# CV_Pot.net
KiCad netlist of a schematic drawn in EAGLE
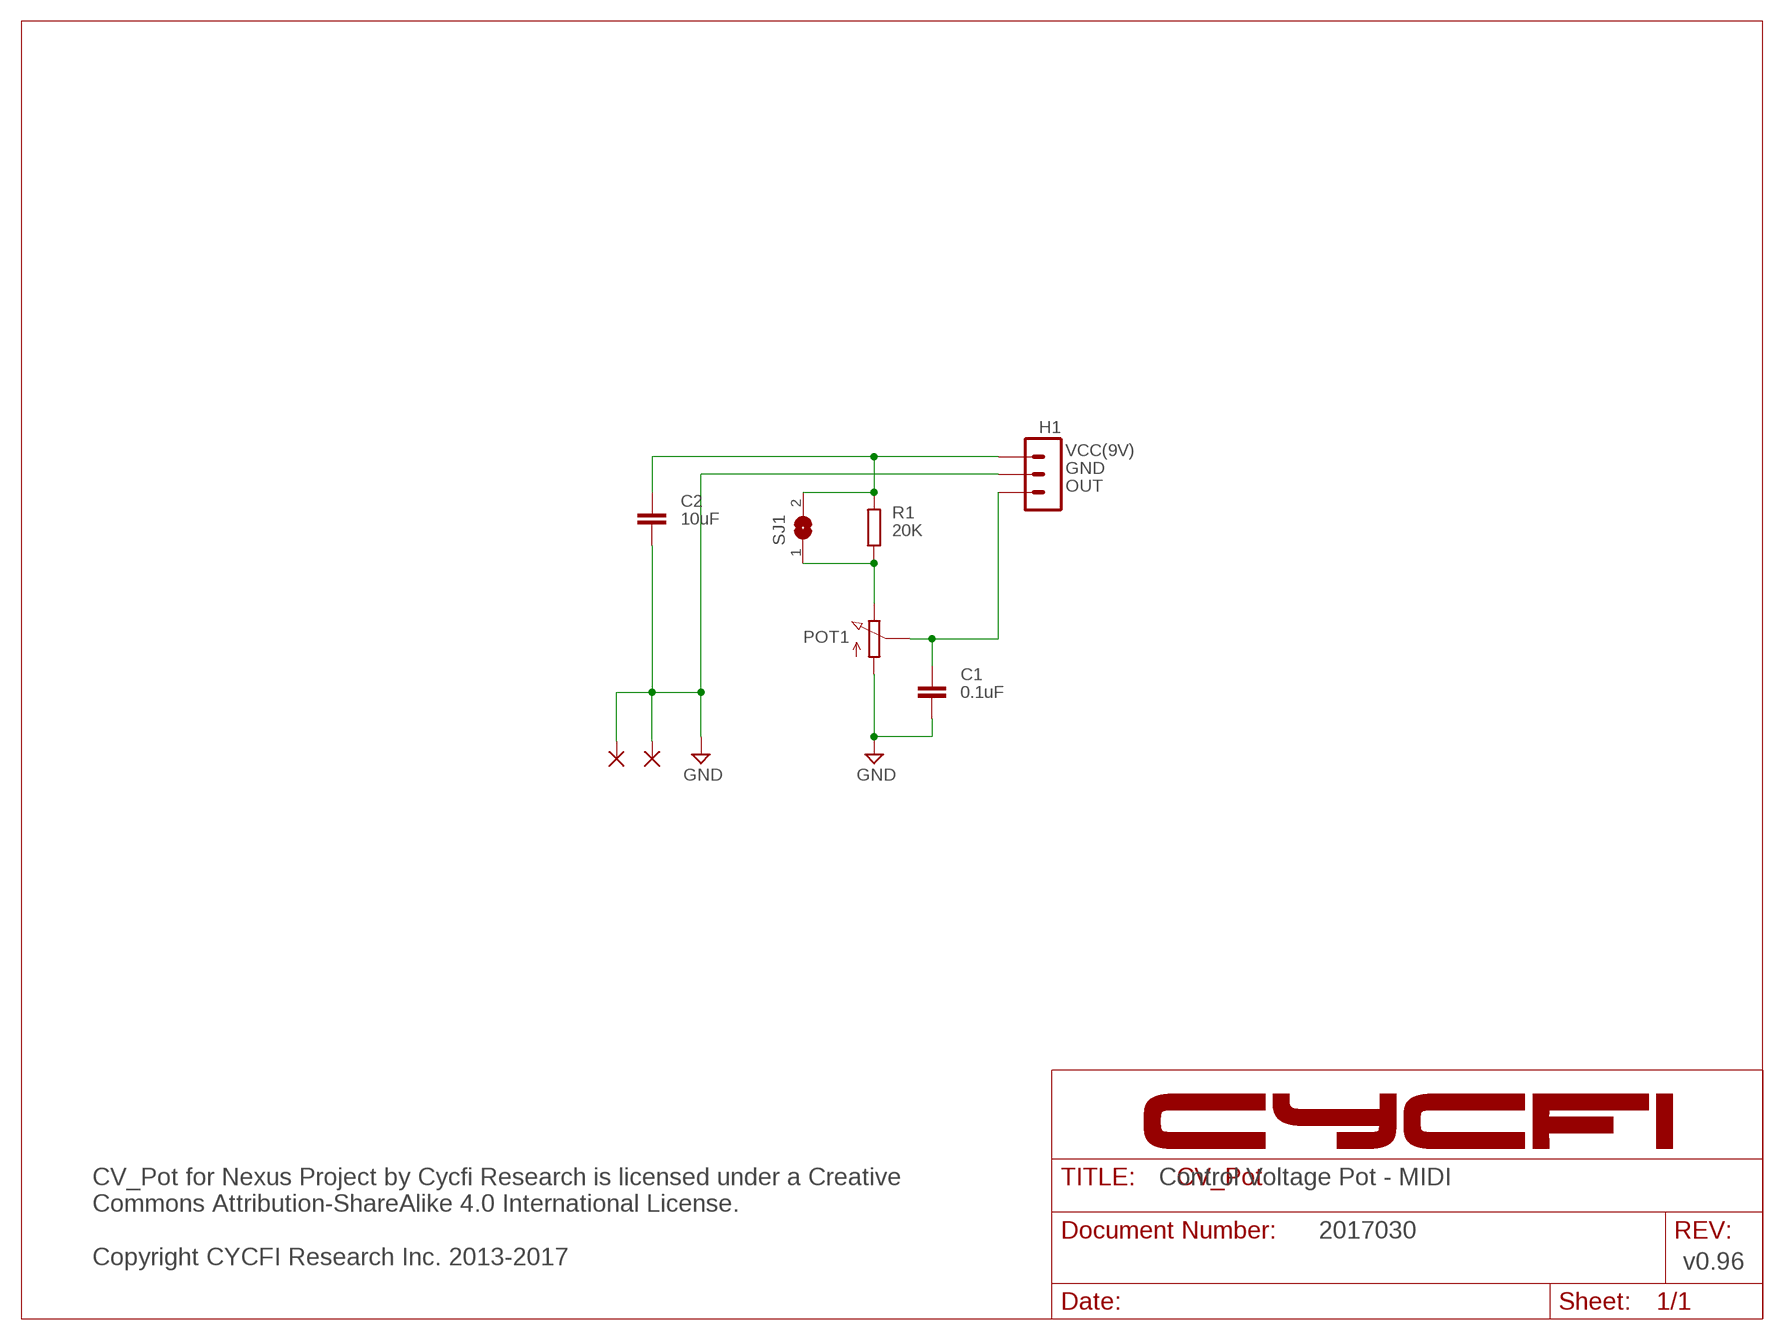
[diagram p0: schematic, sheet 1]

(export (version "E")
  (design (tool "Eeschema 10.0.6"))
  (components
    (comp (ref "C1")
      (value "0.1uF")
      (footprint "eagle-import:C0603")
      (libsource (lib "eagle-import") (part "C-EUC0603"))
    )
    (comp (ref "C2")
      (value "10uF")
      (footprint "eagle-import:C0805")
      (libsource (lib "eagle-import") (part "C-EUC0805"))
    )
    (comp (ref "GND1")
      (value "SMD2")
      (footprint "eagle-import:SMD1,27-2,54")
      (libsource (lib "eagle-import") (part "SMD2"))
    )
    (comp (ref "GND2")
      (value "SMD2")
      (footprint "eagle-import:SMD1,27-2,54")
      (libsource (lib "eagle-import") (part "SMD2"))
    )
    (comp (ref "H1")
      (value "3PIN-SMD-2.54MM")
      (footprint "eagle-import:3P-SMD-2.54MM")
      (libsource (lib "eagle-import") (part "3PIN-SMD-2.54MM"))
    )
    (comp (ref "POT1")
      (value "25K")
      (footprint "eagle-import:POT_EU_PDB181GTR")
      (libsource (lib "eagle-import") (part "POTPDB181GTR"))
    )
    (comp (ref "R1")
      (value "20K")
      (footprint "eagle-import:R0402")
      (libsource (lib "eagle-import") (part "R-EU_R0402"))
    )
    (comp (ref "SJ1") (value "SJ") (footprint "eagle-import:SJ") (libsource (lib "eagle-import") (part "SJ")))
  )
  (nets
    (net (code "1") (name "GND") (class "Default")
      (node (ref "C1") (pin "2") (pinfunction "2_2") (pintype "passive"))
      (node (ref "C2") (pin "2") (pinfunction "2_2") (pintype "passive"))
      (node (ref "GND1") (pin "1") (pinfunction "P_1") (pintype "passive"))
      (node (ref "GND2") (pin "1") (pinfunction "P_1") (pintype "passive"))
      (node (ref "H1") (pin "P$2") (pinfunction "2_P$2") (pintype "passive"))
      (node (ref "POT1") (pin "A1") (pinfunction "1_A1") (pintype "passive"))
    )
    (net (code "2") (name "Net-(H1-1)") (class "Default")
      (node (ref "C1") (pin "1") (pinfunction "1_1") (pintype "passive"))
      (node (ref "H1") (pin "P$1") (pinfunction "1_P$1") (pintype "passive"))
      (node (ref "POT1") (pin "A2") (pinfunction "2_A2") (pintype "passive"))
    )
    (net (code "3") (name "Net-(H1-3)") (class "Default")
      (node (ref "C2") (pin "1") (pinfunction "1_1") (pintype "passive"))
      (node (ref "H1") (pin "P$3") (pinfunction "3_P$3") (pintype "passive"))
      (node (ref "R1") (pin "2") (pinfunction "2_2") (pintype "passive"))
      (node (ref "SJ1") (pin "2") (pinfunction "2_2") (pintype "passive"))
    )
    (net (code "4") (name "Net-(POT1-3)") (class "Default")
      (node (ref "POT1") (pin "A3") (pinfunction "3_A3") (pintype "passive"))
      (node (ref "R1") (pin "1") (pinfunction "1_1") (pintype "passive"))
      (node (ref "SJ1") (pin "1") (pinfunction "1_1") (pintype "passive"))
    )
  )
)
